# XL6019.net
KiCad netlist of a schematic drawn in Altium Designer
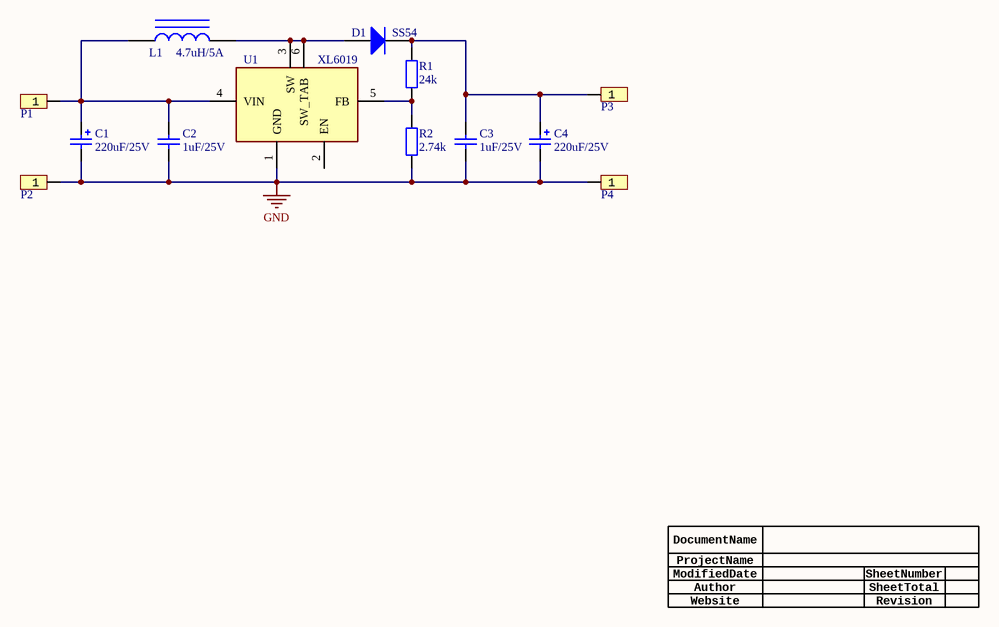
[diagram p0: XL6019.SchDoc]

(export (version "E")
  (design (tool "Eeschema 10.0.6"))
  (components
    (comp (ref "C1")
      (value "220uF/25V")
      (footprint "C_SMD-8X10")
      (description "贴片电容-有极性")
      (libsource (lib "Power_Lib_Altium") (part "CAP-POL"))
    )
    (comp (ref "C2")
      (value "1uF/25V")
      (footprint "CAP-0603")
      (description "贴片电容")
      (libsource (lib "Power_Lib_Altium") (part "CAP"))
    )
    (comp (ref "C3")
      (value "1uF/25V")
      (footprint "CAP-0603")
      (description "贴片电容")
      (libsource (lib "Power_Lib_Altium") (part "CAP"))
    )
    (comp (ref "C4")
      (value "220uF/25V")
      (footprint "C_SMD-8X10")
      (description "贴片电容-有极性")
      (libsource (lib "Power_Lib_Altium") (part "CAP-POL"))
    )
    (comp (ref "D1")
      (value "SS54")
      (footprint "DO-214AA/SMB")
      (description "二极管")
      (libsource (lib "Power_Lib_Altium") (part "DIODE"))
    )
    (comp (ref "L1")
      (value "4.7uH/5A")
      (footprint "L-0630")
      (description "电感")
      (libsource (lib "Power_Lib_Altium") (part "INDUCTOR"))
    )
    (comp (ref "P1")
      (value "HDR1x2_2.54")
      (footprint "HDR1X1_2.54")
      (description "Header")
      (libsource (lib "") (part "HDR1x1_2.54_1"))
    )
    (comp (ref "P2")
      (value "HDR1x2_2.54")
      (footprint "HDR1X1_2.54")
      (description "Header")
      (libsource (lib "") (part "HDR1x1_2.54_1"))
    )
    (comp (ref "P3")
      (value "HDR1x2_2.54")
      (footprint "HDR1X1_2.54")
      (description "Header")
      (libsource (lib "Power_Lib_Altium") (part "HDR1x1_2.54"))
    )
    (comp (ref "P4")
      (value "HDR1x2_2.54")
      (footprint "HDR1X1_2.54")
      (description "Header")
      (libsource (lib "Power_Lib_Altium") (part "HDR1x1_2.54"))
    )
    (comp (ref "R1")
      (value "24k")
      (footprint "R-0603")
      (description "贴片电阻")
      (libsource (lib "Power_Lib_Altium") (part "RES"))
    )
    (comp (ref "R2")
      (value "2.74k")
      (footprint "R-0603")
      (description "贴片电阻")
      (libsource (lib "Power_Lib_Altium") (part "RES"))
    )
    (comp (ref "U1")
      (value "XL6019")
      (footprint "TO-263-5")
      (description "DC-DC")
      (fields (field (name "MANUFACTURER_PART_NUMBER") "FT232RL") (field (name "RS PART NUMBER") "0406580P"))
      (libsource (lib "Power_Lib_Altium") (part "XL6019"))
    )
  )
  (nets
    (net (code "1") (name "GND") (class "Default")
      (node (ref "C1") (pin "2") (pinfunction "2_2") (pintype "passive"))
      (node (ref "C2") (pin "1") (pinfunction "1_1") (pintype "passive"))
      (node (ref "C3") (pin "1") (pinfunction "1_1") (pintype "passive"))
      (node (ref "C4") (pin "2") (pinfunction "2_2") (pintype "passive"))
      (node (ref "P2") (pin "1") (pinfunction "1_1") (pintype "passive"))
      (node (ref "P4") (pin "1") (pinfunction "1_1") (pintype "passive"))
      (node (ref "R2") (pin "1") (pinfunction "1_1") (pintype "passive"))
      (node (ref "U1") (pin "1") (pinfunction "GND_1") (pintype "passive"))
    )
    (net (code "2") (name "Net-(D1-A)") (class "Default")
      (node (ref "D1") (pin "1") (pinfunction "A_1") (pintype "passive"))
      (node (ref "L1") (pin "2") (pinfunction "2_2") (pintype "passive"))
      (node (ref "U1") (pin "3") (pinfunction "SW_3") (pintype "passive"))
      (node (ref "U1") (pin "6") (pinfunction "SW_TAB_6") (pintype "passive"))
    )
    (net (code "3") (name "Net-(D1-K)") (class "Default")
      (node (ref "C3") (pin "2") (pinfunction "2_2") (pintype "passive"))
      (node (ref "C4") (pin "1") (pinfunction "1_1") (pintype "passive"))
      (node (ref "D1") (pin "2") (pinfunction "K_2") (pintype "passive"))
      (node (ref "P3") (pin "1") (pinfunction "1_1") (pintype "passive"))
      (node (ref "R1") (pin "2") (pinfunction "2_2") (pintype "passive"))
    )
    (net (code "4") (name "Net-(U1-FB)") (class "Default")
      (node (ref "R1") (pin "1") (pinfunction "1_1") (pintype "passive"))
      (node (ref "R2") (pin "2") (pinfunction "2_2") (pintype "passive"))
      (node (ref "U1") (pin "5") (pinfunction "FB_5") (pintype "power_in"))
    )
    (net (code "5") (name "Net-(U1-VIN)") (class "Default")
      (node (ref "C1") (pin "1") (pinfunction "1_1") (pintype "passive"))
      (node (ref "C2") (pin "2") (pinfunction "2_2") (pintype "passive"))
      (node (ref "L1") (pin "1") (pinfunction "1_1") (pintype "passive"))
      (node (ref "P1") (pin "1") (pinfunction "1_1") (pintype "passive"))
      (node (ref "U1") (pin "4") (pinfunction "VIN_4") (pintype "power_in"))
    )
    (net (code "6") (name "unconnected-(U1-EN-Pad2)") (class "Default")
      (node (ref "U1") (pin "2") (pinfunction "EN_2") (pintype "passive"))
    )
  )
)
